# Schematic_Open-Book.net
KiCad netlist of a schematic drawn in EAGLE
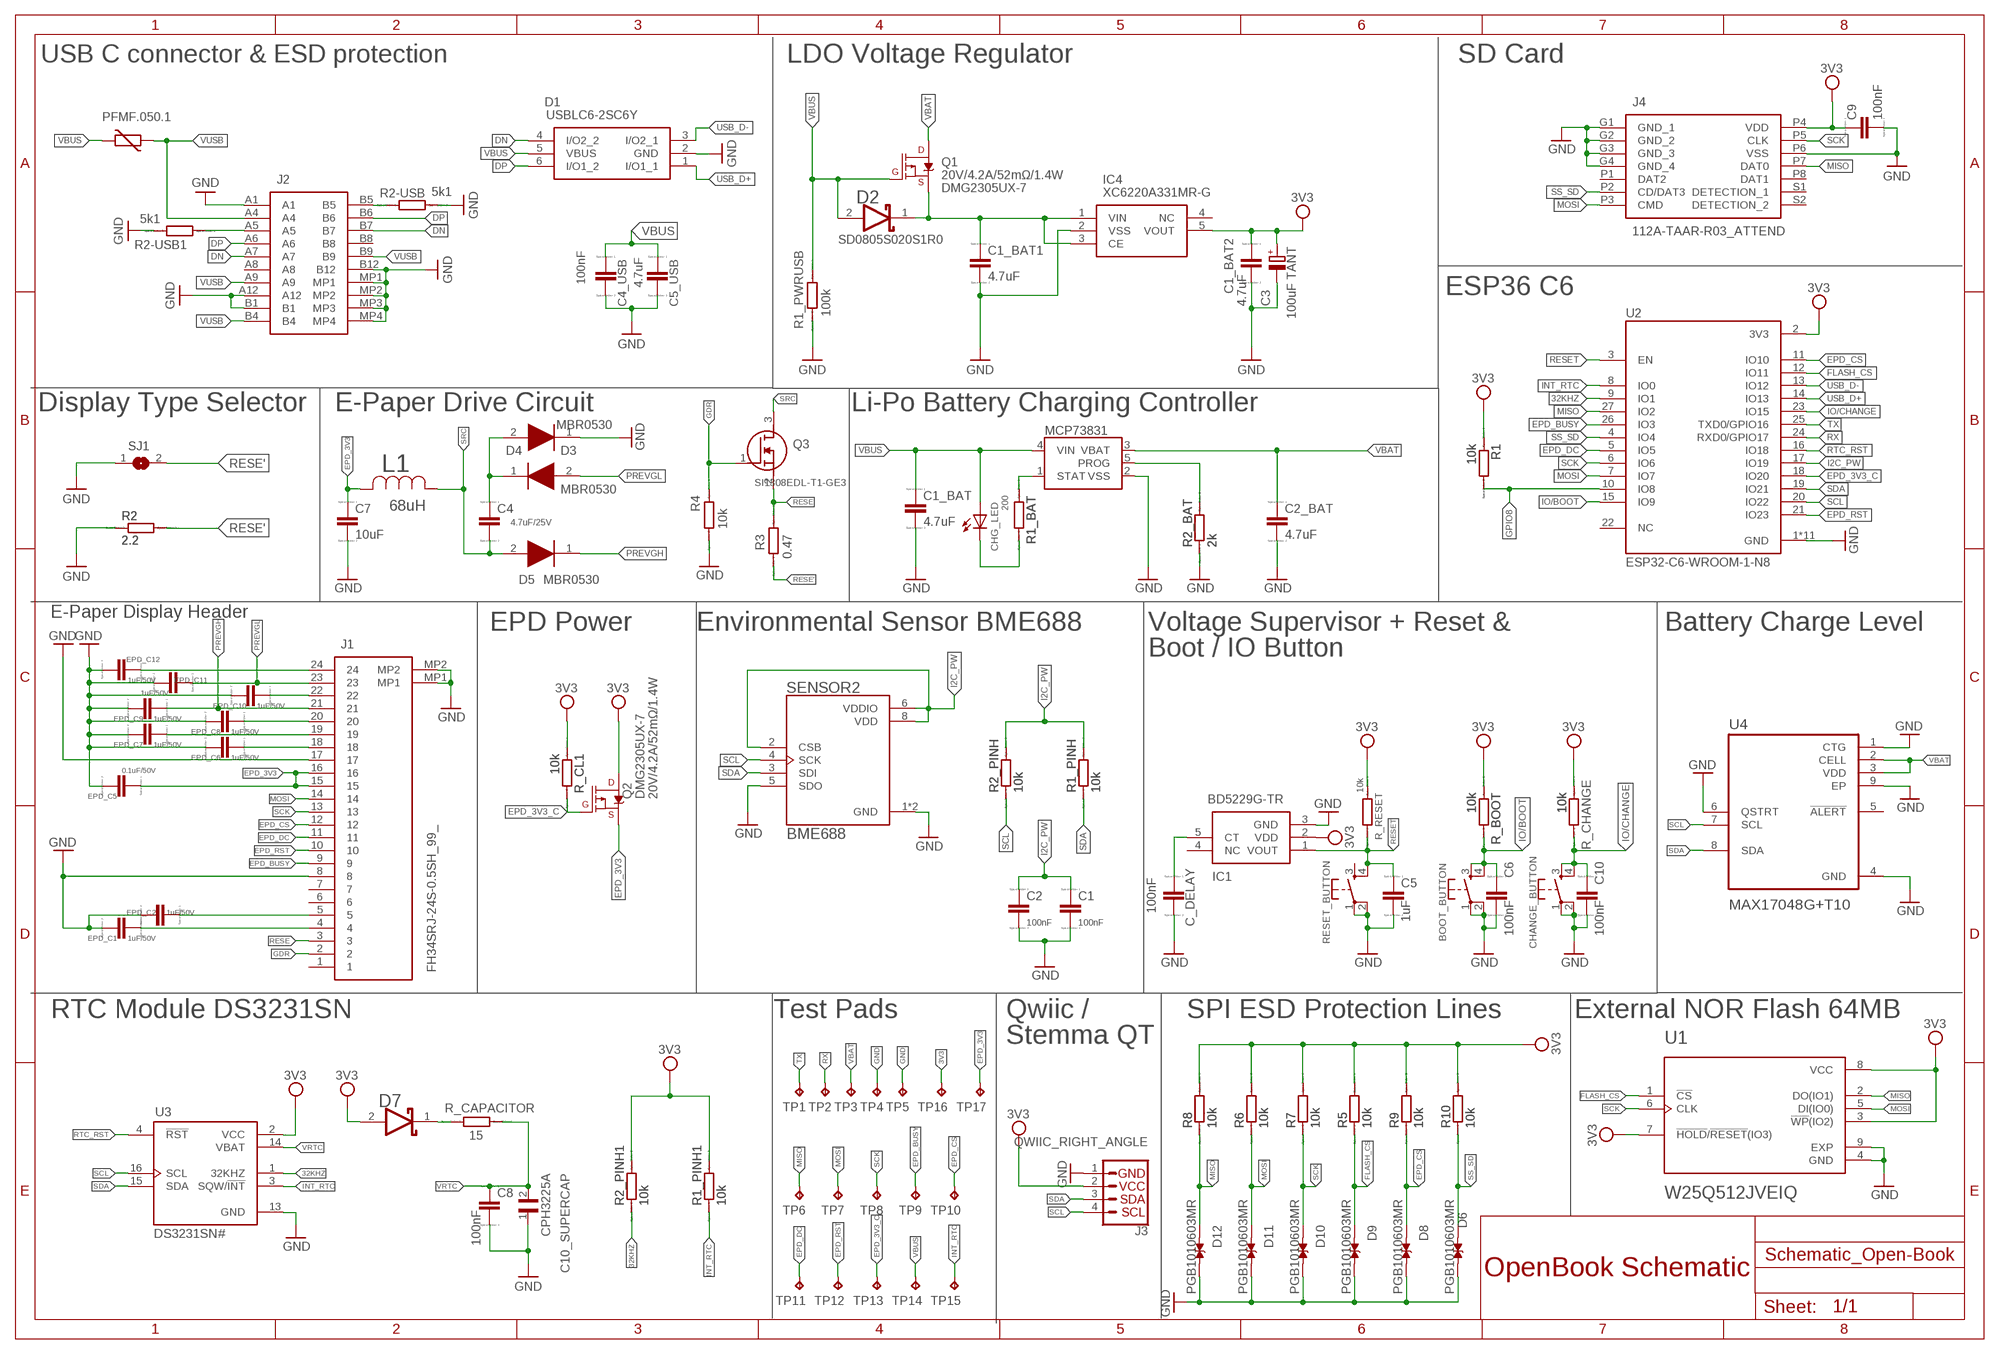
[diagram p0: schematic, sheet 1]

(export (version "E")
  (design (tool "Eeschema 10.0.6"))
  (components
    (comp (ref "BOOT_BUTTON")
      (value "BOOT_BUTTON")
      (footprint "eagle-import:MYBUTTON")
      (libsource (lib "eagle-import") (part "BUTTON_CUSYOMV1"))
    )
    (comp (ref "C1")
      (value "100nF")
      (footprint "eagle-import:ESP32_WROVER_EAGLE-LTSPICE_C0402")
      (libsource (lib "eagle-import") (part "ESP32_WROVER_EAGLE-LTSPICE_CC0402"))
    )
    (comp (ref "C1_BAT")
      (value "4.7uF")
      (footprint "eagle-import:ESP32_WROVER_EAGLE-LTSPICE_C0402")
      (libsource (lib "eagle-import") (part "ESP32_WROVER_EAGLE-LTSPICE_CC0402"))
    )
    (comp (ref "C1_BAT1")
      (value "4.7uF")
      (footprint "eagle-import:ESP32_WROVER_EAGLE-LTSPICE_C0402")
      (libsource (lib "eagle-import") (part "ESP32_WROVER_EAGLE-LTSPICE_CC0402"))
    )
    (comp (ref "C1_BAT2")
      (value "4.7uF")
      (footprint "eagle-import:ESP32_WROVER_EAGLE-LTSPICE_C0402")
      (libsource (lib "eagle-import") (part "ESP32_WROVER_EAGLE-LTSPICE_CC0402"))
    )
    (comp (ref "C2")
      (value "100nF")
      (footprint "eagle-import:ESP32_WROVER_EAGLE-LTSPICE_C0402")
      (libsource (lib "eagle-import") (part "ESP32_WROVER_EAGLE-LTSPICE_CC0402"))
    )
    (comp (ref "C2_BAT")
      (value "4.7uF")
      (footprint "eagle-import:ESP32_WROVER_EAGLE-LTSPICE_C0402")
      (libsource (lib "eagle-import") (part "ESP32_WROVER_EAGLE-LTSPICE_CC0402"))
    )
    (comp (ref "C3")
      (value "100uF TANT")
      (footprint "eagle-import:RCL_CT3528")
      (libsource (lib "eagle-import") (part "RCL_CPOL-EUCT3528"))
    )
    (comp (ref "C4")
      (value "4.7uF/25V")
      (footprint "eagle-import:ESP32_WROVER_EAGLE-LTSPICE_C0402")
      (libsource (lib "eagle-import") (part "ESP32_WROVER_EAGLE-LTSPICE_CC0402"))
    )
    (comp (ref "C4_USB")
      (value "100nF")
      (footprint "eagle-import:EAGLE-LTSPICE_C0402")
      (libsource (lib "eagle-import") (part "EAGLE-LTSPICE_CC0402"))
    )
    (comp (ref "C5")
      (value "1uF")
      (footprint "eagle-import:ESP32_WROVER_EAGLE-LTSPICE_C0402")
      (libsource (lib "eagle-import") (part "ESP32_WROVER_EAGLE-LTSPICE_CC0402"))
    )
    (comp (ref "C5_USB")
      (value "4.7uF")
      (footprint "eagle-import:EAGLE-LTSPICE_C0402")
      (libsource (lib "eagle-import") (part "EAGLE-LTSPICE_CC0402"))
    )
    (comp (ref "C6")
      (value "100nF")
      (footprint "eagle-import:ESP32_WROVER_EAGLE-LTSPICE_C0402")
      (libsource (lib "eagle-import") (part "ESP32_WROVER_EAGLE-LTSPICE_CC0402"))
    )
    (comp (ref "C7")
      (value "10uF")
      (footprint "eagle-import:ESP32_WROVER_EAGLE-LTSPICE_C0402")
      (libsource (lib "eagle-import") (part "ESP32_WROVER_EAGLE-LTSPICE_CC0402"))
    )
    (comp (ref "C8")
      (value "100nF")
      (footprint "eagle-import:ESP32_WROVER_EAGLE-LTSPICE_C0402")
      (libsource (lib "eagle-import") (part "ESP32_WROVER_EAGLE-LTSPICE_CC0402"))
    )
    (comp (ref "C9")
      (value "100nF")
      (footprint "eagle-import:ESP32_WROVER_EAGLE-LTSPICE_C0402")
      (libsource (lib "eagle-import") (part "ESP32_WROVER_EAGLE-LTSPICE_CC0402"))
    )
    (comp (ref "C10")
      (value "100nF")
      (footprint "eagle-import:ESP32_WROVER_EAGLE-LTSPICE_C0402")
      (libsource (lib "eagle-import") (part "ESP32_WROVER_EAGLE-LTSPICE_CC0402"))
    )
    (comp (ref "C10_SUPERCAP")
      (value "CPH3225A")
      (footprint "eagle-import:CAPCP3225X100N")
      (fields (field (name "MF") "Seiko Instruments"))
      (libsource (lib "eagle-import") (part "CPH3225A"))
    )
    (comp (ref "CHANGE_BUTTON")
      (value "CHANGE_BUTTON")
      (footprint "eagle-import:MYBUTTON")
      (libsource (lib "eagle-import") (part "BUTTON_CUSYOMV1"))
    )
    (comp (ref "CHG_LED")
      (value "ADAFRUIT_LEDCHIP-LED0603")
      (footprint "eagle-import:ADAFRUIT_CHIP-LED0603")
      (libsource (lib "eagle-import") (part "ADAFRUIT_LEDCHIP-LED0603"))
    )
    (comp (ref "C_DELAY")
      (value "100nF")
      (footprint "eagle-import:ESP32_WROVER_EAGLE-LTSPICE_C0402")
      (libsource (lib "eagle-import") (part "ESP32_WROVER_EAGLE-LTSPICE_CC0402"))
    )
    (comp (ref "D1")
      (value "USBLC6-2SC6Y")
      (footprint "eagle-import:SOT95P280X145-6N")
      (fields (field (name "MF") "STMicroelectronics"))
      (libsource (lib "eagle-import") (part "USBLC6-2SC6Y"))
    )
    (comp (ref "D2")
      (value "ESP32_WROVER_AVX---SD0805S020S1R0_AVX_SD0805S020S1R0_0_0AVX_SD0805S020S1R0_0_0")
      (footprint "eagle-import:ESP32_WROVER_AVX---SD0805S020S1R0_AVX_SD0805S020S1R0_0")
      (fields
        (field (name "DIGIKEY_PART_NUMBER") "478-7800-1-ND")
        (field (name "MF") "AVX")
        (field (name "MOUSER_PART_NUMBER") "581-SD0805S020S1R0")
      )
      (libsource (lib "eagle-import") (part "ESP32_WROVER_AVX---SD0805S020S1R0_AVX_SD0805S020S1R0_0_0AVX_SD0805S020S1R0_0_0"))
    )
    (comp (ref "D3")
      (value "MBR0530")
      (footprint "eagle-import:SOD3716X135N")
      (fields (field (name "MF") "ON Semiconductor"))
      (libsource (lib "eagle-import") (part "MBR0530"))
    )
    (comp (ref "D4")
      (value "MBR0530")
      (footprint "eagle-import:SOD3716X135N")
      (fields (field (name "MF") "ON Semiconductor"))
      (libsource (lib "eagle-import") (part "MBR0530"))
    )
    (comp (ref "D5")
      (value "MBR0530")
      (footprint "eagle-import:SOD3716X135N")
      (fields (field (name "MF") "ON Semiconductor"))
      (libsource (lib "eagle-import") (part "MBR0530"))
    )
    (comp (ref "D6")
      (value "PGB1010603MR")
      (footprint "eagle-import:DIOC1608X36N")
      (fields (field (name "MF") "Littelfuse Inc."))
      (libsource (lib "eagle-import") (part "PGB1010603MR"))
    )
    (comp (ref "D7")
      (value "ESP32_WROVER_AVX---SD0805S020S1R0_AVX_SD0805S020S1R0_0_0AVX_SD0805S020S1R0_0_0")
      (footprint "eagle-import:ESP32_WROVER_AVX---SD0805S020S1R0_AVX_SD0805S020S1R0_0")
      (fields
        (field (name "DIGIKEY_PART_NUMBER") "478-7800-1-ND")
        (field (name "MF") "AVX")
        (field (name "MOUSER_PART_NUMBER") "581-SD0805S020S1R0")
      )
      (libsource (lib "eagle-import") (part "ESP32_WROVER_AVX---SD0805S020S1R0_AVX_SD0805S020S1R0_0_0AVX_SD0805S020S1R0_0_0"))
    )
    (comp (ref "D8")
      (value "PGB1010603MR")
      (footprint "eagle-import:DIOC1608X36N")
      (fields (field (name "MF") "Littelfuse Inc."))
      (libsource (lib "eagle-import") (part "PGB1010603MR"))
    )
    (comp (ref "D9")
      (value "PGB1010603MR")
      (footprint "eagle-import:DIOC1608X36N")
      (fields (field (name "MF") "Littelfuse Inc."))
      (libsource (lib "eagle-import") (part "PGB1010603MR"))
    )
    (comp (ref "D10")
      (value "PGB1010603MR")
      (footprint "eagle-import:DIOC1608X36N")
      (fields (field (name "MF") "Littelfuse Inc."))
      (libsource (lib "eagle-import") (part "PGB1010603MR"))
    )
    (comp (ref "D11")
      (value "PGB1010603MR")
      (footprint "eagle-import:DIOC1608X36N")
      (fields (field (name "MF") "Littelfuse Inc."))
      (libsource (lib "eagle-import") (part "PGB1010603MR"))
    )
    (comp (ref "D12")
      (value "PGB1010603MR")
      (footprint "eagle-import:DIOC1608X36N")
      (fields (field (name "MF") "Littelfuse Inc."))
      (libsource (lib "eagle-import") (part "PGB1010603MR"))
    )
    (comp (ref "EPD_C1")
      (value "1uF/50V")
      (footprint "eagle-import:ESP32_WROVER_EAGLE-LTSPICE_C0402")
      (libsource (lib "eagle-import") (part "ESP32_WROVER_EAGLE-LTSPICE_CC0402"))
    )
    (comp (ref "EPD_C2")
      (value "1uF/50V")
      (footprint "eagle-import:ESP32_WROVER_EAGLE-LTSPICE_C0402")
      (libsource (lib "eagle-import") (part "ESP32_WROVER_EAGLE-LTSPICE_CC0402"))
    )
    (comp (ref "EPD_C5")
      (value "0.1uF/50V")
      (footprint "eagle-import:EAGLE-LTSPICE_C0402")
      (libsource (lib "eagle-import") (part "EAGLE-LTSPICE_CC0402"))
    )
    (comp (ref "EPD_C6")
      (value "1uF/50V")
      (footprint "eagle-import:EAGLE-LTSPICE_C0402")
      (libsource (lib "eagle-import") (part "EAGLE-LTSPICE_CC0402"))
    )
    (comp (ref "EPD_C7")
      (value "1uF/50V")
      (footprint "eagle-import:EAGLE-LTSPICE_C0402")
      (libsource (lib "eagle-import") (part "EAGLE-LTSPICE_CC0402"))
    )
    (comp (ref "EPD_C8")
      (value "1uF/50V")
      (footprint "eagle-import:EAGLE-LTSPICE_C0402")
      (libsource (lib "eagle-import") (part "EAGLE-LTSPICE_CC0402"))
    )
    (comp (ref "EPD_C9")
      (value "1uF/50V")
      (footprint "eagle-import:EAGLE-LTSPICE_C0402")
      (libsource (lib "eagle-import") (part "EAGLE-LTSPICE_CC0402"))
    )
    (comp (ref "EPD_C10")
      (value "1uF/50V")
      (footprint "eagle-import:EAGLE-LTSPICE_C0402")
      (libsource (lib "eagle-import") (part "EAGLE-LTSPICE_CC0402"))
    )
    (comp (ref "EPD_C11")
      (value "1uF/50V")
      (footprint "eagle-import:EAGLE-LTSPICE_C0402")
      (libsource (lib "eagle-import") (part "EAGLE-LTSPICE_CC0402"))
    )
    (comp (ref "EPD_C12")
      (value "1uF/50V")
      (footprint "eagle-import:EAGLE-LTSPICE_C0402")
      (libsource (lib "eagle-import") (part "EAGLE-LTSPICE_CC0402"))
    )
    (comp (ref "IC1")
      (value "BD5229G-TR")
      (footprint "eagle-import:SOT95P280X125-5N")
      (fields (field (name "MOUSER_PART_NUMBER") "755-BD5229G-TR"))
      (libsource (lib "eagle-import") (part "BD5229G-TR"))
    )
    (comp (ref "IC4")
      (value "XC6220A331MR-G")
      (footprint "eagle-import:SOT95P280X120-5N")
      (fields (field (name "MOUSER_PART_NUMBER") "865-XC6220A331MR-G"))
      (libsource (lib "eagle-import") (part "XC6220A331MR-G"))
    )
    (comp (ref "J1")
      (value "FH34SRJ-24S-0.5SH_99_")
      (footprint "eagle-import:FH34SRJ24S05SH99")
      (fields
        (field (name "MANUFACTURER_PART_NUMBER") "FH34SRJ-24S-0.5SH(99)")
        (field (name "MOUSER_PART_NUMBER") "798-FH34SRJ24S05SH99")
      )
      (libsource (lib "eagle-import") (part "FH34SRJ-24S-0.5SH_99_"))
    )
    (comp (ref "J2")
      (value "SAMACSYS_PARTS_USB4110-GF-A")
      (footprint "eagle-import:SAMACSYS_PARTS_USB4110GFA")
      (fields
        (field (name "MANUFACTURER_PART_NUMBER") "USB4110-GF-A")
        (field (name "MOUSER_PART_NUMBER") "640-USB4110-GF-A")
      )
      (libsource (lib "eagle-import") (part "SAMACSYS_PARTS_USB4110-GF-A"))
    )
    (comp (ref "J3")
      (value "QWIIC_RIGHT_ANGLE")
      (footprint "eagle-import:JST04_1MM_RA")
      (libsource (lib "eagle-import") (part "QWIIC_CONNECTORJS-1MM"))
    )
    (comp (ref "J4")
      (value "112A-TAAR-R03_ATTEND")
      (footprint "eagle-import:112ATAARR03ATTEND")
      (fields (field (name "MANUFACTURER_PART_NUMBER") "112A-TAAR-R03 ATTEND"))
      (libsource (lib "eagle-import") (part "112A-TAAR-R03_ATTEND"))
    )
    (comp (ref "L1")
      (value "68uH")
      (footprint "eagle-import:IND_4828-WE-TPC_WRE")
      (fields
        (field (name "MANUFACTURER_PART_NUMBER") "744043680")
        (field (name "COPYRIGHT") "Copyright (C) 2024 Ultra Librarian. All rights reserved.")
      )
      (libsource (lib "eagle-import") (part "744043680IND_4828-WE-TPC_WRE"))
    )
    (comp (ref "MCP73831")
      (value "ESP32_WROVER_SPARKFUN-IC-POWER_MCP73831")
      (footprint "eagle-import:ESP32_WROVER_SPARKFUN-IC-POWER_SOT23-5")
      (libsource (lib "eagle-import") (part "ESP32_WROVER_SPARKFUN-IC-POWER_MCP73831"))
    )
    (comp (ref "PFMF.050.1")
      (value "ESP32C6_VARISTORCN1812")
      (footprint "eagle-import:ESP32C6_VARISTOR_CT_CN1812")
      (libsource (lib "eagle-import") (part "ESP32C6_VARISTORCN1812"))
    )
    (comp (ref "Q1")
      (value "20V/4.2A/52mΩ/1.4W")
      (footprint "eagle-import:ESP32_WROVER_SPARKFUN-DISCRETESEMI_SOT23-3")
      (libsource (lib "eagle-import") (part "ESP32_WROVER_SPARKFUN-DISCRETESEMI_MOSFET_PCH-DMG2305UX-7"))
    )
    (comp (ref "Q2")
      (value "20V/4.2A/52mΩ/1.4W")
      (footprint "eagle-import:ESP32_WROVER_SPARKFUN-DISCRETESEMI_SOT23-3")
      (libsource (lib "eagle-import") (part "ESP32_WROVER_SPARKFUN-DISCRETESEMI_MOSFET_PCH-DMG2305UX-7"))
    )
    (comp (ref "Q3")
      (value "SI1308EDL-T1-GE3")
      (footprint "eagle-import:SOT65P210X110-3N")
      (fields (field (name "MF") "Vishay Siliconix"))
      (libsource (lib "eagle-import") (part "SI1308EDL-T1-GE3"))
    )
    (comp (ref "R1")
      (value "10k")
      (footprint "eagle-import:ESP32_WROVER_EAGLE-LTSPICE_R0402")
      (libsource (lib "eagle-import") (part "ESP32_WROVER_EAGLE-LTSPICE_RR0402"))
    )
    (comp (ref "R1_BAT")
      (value "200")
      (footprint "eagle-import:ESP32_WROVER_EAGLE-LTSPICE_R0402")
      (libsource (lib "eagle-import") (part "ESP32_WROVER_EAGLE-LTSPICE_RR0402"))
    )
    (comp (ref "R1_PINH")
      (value "10k")
      (footprint "eagle-import:ESP32_WROVER_EAGLE-LTSPICE_R0402")
      (libsource (lib "eagle-import") (part "ESP32_WROVER_EAGLE-LTSPICE_RR0402"))
    )
    (comp (ref "R1_PINH1")
      (value "10k")
      (footprint "eagle-import:ESP32_WROVER_EAGLE-LTSPICE_R0402")
      (libsource (lib "eagle-import") (part "ESP32_WROVER_EAGLE-LTSPICE_RR0402"))
    )
    (comp (ref "R1_PWRUSB")
      (value "100k")
      (footprint "eagle-import:ESP32_WROVER_EAGLE-LTSPICE_R0402")
      (libsource (lib "eagle-import") (part "ESP32_WROVER_EAGLE-LTSPICE_RR0402"))
    )
    (comp (ref "R2")
      (value "2.2")
      (footprint "eagle-import:ESP32_WROVER_EAGLE-LTSPICE_R0402")
      (libsource (lib "eagle-import") (part "ESP32_WROVER_EAGLE-LTSPICE_RR0402"))
    )
    (comp (ref "R2-USB")
      (value "5k1")
      (footprint "eagle-import:ESP32_WROVER_EAGLE-LTSPICE_R0402")
      (libsource (lib "eagle-import") (part "ESP32_WROVER_EAGLE-LTSPICE_RR0402"))
    )
    (comp (ref "R2-USB1")
      (value "5k1")
      (footprint "eagle-import:ESP32_WROVER_EAGLE-LTSPICE_R0402")
      (libsource (lib "eagle-import") (part "ESP32_WROVER_EAGLE-LTSPICE_RR0402"))
    )
    (comp (ref "R2_BAT")
      (value "2k")
      (footprint "eagle-import:ESP32_WROVER_EAGLE-LTSPICE_R0402")
      (libsource (lib "eagle-import") (part "ESP32_WROVER_EAGLE-LTSPICE_RR0402"))
    )
    (comp (ref "R2_PINH")
      (value "10k")
      (footprint "eagle-import:ESP32_WROVER_EAGLE-LTSPICE_R0402")
      (libsource (lib "eagle-import") (part "ESP32_WROVER_EAGLE-LTSPICE_RR0402"))
    )
    (comp (ref "R2_PINH1")
      (value "10k")
      (footprint "eagle-import:ESP32_WROVER_EAGLE-LTSPICE_R0402")
      (libsource (lib "eagle-import") (part "ESP32_WROVER_EAGLE-LTSPICE_RR0402"))
    )
    (comp (ref "R3")
      (value "0.47")
      (footprint "eagle-import:ESP32_WROVER_EAGLE-LTSPICE_R0402")
      (libsource (lib "eagle-import") (part "ESP32_WROVER_EAGLE-LTSPICE_RR0402"))
    )
    (comp (ref "R4")
      (value "10k")
      (footprint "eagle-import:ESP32_WROVER_EAGLE-LTSPICE_R0402")
      (libsource (lib "eagle-import") (part "ESP32_WROVER_EAGLE-LTSPICE_RR0402"))
    )
    (comp (ref "R5")
      (value "10k")
      (footprint "eagle-import:ESP32_WROVER_EAGLE-LTSPICE_R0402")
      (libsource (lib "eagle-import") (part "ESP32_WROVER_EAGLE-LTSPICE_RR0402"))
    )
    (comp (ref "R6")
      (value "10k")
      (footprint "eagle-import:ESP32_WROVER_EAGLE-LTSPICE_R0402")
      (libsource (lib "eagle-import") (part "ESP32_WROVER_EAGLE-LTSPICE_RR0402"))
    )
    (comp (ref "R7")
      (value "10k")
      (footprint "eagle-import:ESP32_WROVER_EAGLE-LTSPICE_R0402")
      (libsource (lib "eagle-import") (part "ESP32_WROVER_EAGLE-LTSPICE_RR0402"))
    )
    (comp (ref "R8")
      (value "10k")
      (footprint "eagle-import:ESP32_WROVER_EAGLE-LTSPICE_R0402")
      (libsource (lib "eagle-import") (part "ESP32_WROVER_EAGLE-LTSPICE_RR0402"))
    )
    (comp (ref "R9")
      (value "10k")
      (footprint "eagle-import:ESP32_WROVER_EAGLE-LTSPICE_R0402")
      (libsource (lib "eagle-import") (part "ESP32_WROVER_EAGLE-LTSPICE_RR0402"))
    )
    (comp (ref "R10")
      (value "10k")
      (footprint "eagle-import:ESP32_WROVER_EAGLE-LTSPICE_R0402")
      (libsource (lib "eagle-import") (part "ESP32_WROVER_EAGLE-LTSPICE_RR0402"))
    )
    (comp (ref "RESET_BUTTON")
      (value "RESET_BUTTON")
      (footprint "eagle-import:MYBUTTON")
      (libsource (lib "eagle-import") (part "BUTTON_CUSYOMV1"))
    )
    (comp (ref "R_BOOT")
      (value "10k")
      (footprint "eagle-import:ESP32_WROVER_EAGLE-LTSPICE_R0402")
      (libsource (lib "eagle-import") (part "ESP32_WROVER_EAGLE-LTSPICE_RR0402"))
    )
    (comp (ref "R_CAPACITOR")
      (value "15")
      (footprint "eagle-import:ESP32_WROVER_EAGLE-LTSPICE_R0402")
      (libsource (lib "eagle-import") (part "ESP32_WROVER_EAGLE-LTSPICE_RR0402"))
    )
    (comp (ref "R_CHANGE")
      (value "10k")
      (footprint "eagle-import:ESP32_WROVER_EAGLE-LTSPICE_R0402")
      (libsource (lib "eagle-import") (part "ESP32_WROVER_EAGLE-LTSPICE_RR0402"))
    )
    (comp (ref "R_CL1")
      (value "10k")
      (footprint "eagle-import:ESP32_WROVER_EAGLE-LTSPICE_R0402")
      (libsource (lib "eagle-import") (part "ESP32_WROVER_EAGLE-LTSPICE_RR0402"))
    )
    (comp (ref "R_RESET")
      (value "10k")
      (footprint "eagle-import:ESP32_WROVER_EAGLE-LTSPICE_R0402")
      (libsource (lib "eagle-import") (part "ESP32_WROVER_EAGLE-LTSPICE_RR0402"))
    )
    (comp (ref "SENSOR2")
      (value "BME688")
      (footprint "eagle-import:ESP32_WROVER_BME680_PSON80P300X300X100-8N")
      (fields (field (name "MF") "Bosch Sensortec") (field (name "MP") "BME680"))
      (libsource (lib "eagle-import") (part "ESP32_WROVER_BME680_BME680"))
    )
    (comp (ref "SJ1") (value "SJ") (footprint "eagle-import:SJ") (libsource (lib "eagle-import") (part "SJ")))
    (comp (ref "TP1")
      (value "TPTP20R")
      (footprint "eagle-import:TP20R")
      (libsource (lib "eagle-import") (part "TPTP20R"))
    )
    (comp (ref "TP2")
      (value "TPTP20R")
      (footprint "eagle-import:TP20R")
      (libsource (lib "eagle-import") (part "TPTP20R"))
    )
    (comp (ref "TP3")
      (value "TPTP20R")
      (footprint "eagle-import:TP20R")
      (libsource (lib "eagle-import") (part "TPTP20R"))
    )
    (comp (ref "TP4")
      (value "TPTP20R")
      (footprint "eagle-import:TP20R")
      (libsource (lib "eagle-import") (part "TPTP20R"))
    )
    (comp (ref "TP5")
      (value "TPTP20R")
      (footprint "eagle-import:TP20R")
      (libsource (lib "eagle-import") (part "TPTP20R"))
    )
    (comp (ref "TP6")
      (value "TPTP20R")
      (footprint "eagle-import:TP20R")
      (libsource (lib "eagle-import") (part "TPTP20R"))
    )
    (comp (ref "TP7")
      (value "TPTP20R")
      (footprint "eagle-import:TP20R")
      (libsource (lib "eagle-import") (part "TPTP20R"))
    )
    (comp (ref "TP8")
      (value "TPTP20R")
      (footprint "eagle-import:TP20R")
      (libsource (lib "eagle-import") (part "TPTP20R"))
    )
    (comp (ref "TP9")
      (value "TPTP20R")
      (footprint "eagle-import:TP20R")
      (libsource (lib "eagle-import") (part "TPTP20R"))
    )
    (comp (ref "TP10")
      (value "TPTP20R")
      (footprint "eagle-import:TP20R")
      (libsource (lib "eagle-import") (part "TPTP20R"))
    )
    (comp (ref "TP11")
      (value "TPTP20R")
      (footprint "eagle-import:TP20R")
      (libsource (lib "eagle-import") (part "TPTP20R"))
    )
    (comp (ref "TP12")
      (value "TPTP20R")
      (footprint "eagle-import:TP20R")
      (libsource (lib "eagle-import") (part "TPTP20R"))
    )
    (comp (ref "TP13")
      (value "TPTP20R")
      (footprint "eagle-import:TP20R")
      (libsource (lib "eagle-import") (part "TPTP20R"))
    )
    (comp (ref "TP14")
      (value "TPTP20R")
      (footprint "eagle-import:TP20R")
      (libsource (lib "eagle-import") (part "TPTP20R"))
    )
    (comp (ref "TP15")
      (value "TPTP20R")
      (footprint "eagle-import:TP20R")
      (libsource (lib "eagle-import") (part "TPTP20R"))
    )
    (comp (ref "TP16")
      (value "TPTP20R")
      (footprint "eagle-import:TP20R")
      (libsource (lib "eagle-import") (part "TPTP20R"))
    )
    (comp (ref "TP17")
      (value "TPTP20R")
      (footprint "eagle-import:TP20R")
      (libsource (lib "eagle-import") (part "TPTP20R"))
    )
    (comp (ref "U1")
      (value "W25Q512JVEIQ")
      (footprint "eagle-import:SON127P600X800X80-9N")
      (fields (field (name "MF") "Winbond Electronics"))
      (libsource (lib "eagle-import") (part "W25Q512JVEIQ"))
    )
    (comp (ref "U2")
      (value "ESP32-C6-WROOM-1-N8")
      (footprint "eagle-import:XCVR_ESP32-C6-WROOM-1-N8")
      (fields (field (name "MF") "Espressif Systems"))
      (libsource (lib "eagle-import") (part "ESP32-C6-WROOM-1-N8"))
    )
    (comp (ref "U3")
      (value "DS3231SN#")
      (footprint "eagle-import:SOIC127P1032X265-16N")
      (fields (field (name "MF") "Analog Devices"))
      (libsource (lib "eagle-import") (part "DS3231SN#"))
    )
    (comp (ref "U4")
      (value "MAX17048G+T10")
      (footprint "eagle-import:SON50P200X200X80-9N")
      (fields (field (name "MF") "Analog Devices"))
      (libsource (lib "eagle-import") (part "MAX17048G+T10"))
    )
  )
  (nets
    (net (code "1") (name "3V3") (class "Default")
      (node (ref "C1_BAT2") (pin "1") (pinfunction "1_1") (pintype "passive"))
      (node (ref "C3") (pin "+") (pinfunction "+_+") (pintype "passive"))
      (node (ref "C9") (pin "1") (pinfunction "1_1") (pintype "passive"))
      (node (ref "D7") (pin "2") (pinfunction "ANODE_2") (pintype "bidirectional"))
      (node (ref "IC1") (pin "2") (pinfunction "VDD_2") (pintype "bidirectional"))
      (node (ref "IC4") (pin "5") (pinfunction "VOUT_5") (pintype "bidirectional"))
      (node (ref "J3") (pin "2") (pinfunction "2_2") (pintype "power_in"))
      (node (ref "J4") (pin "P4") (pinfunction "VDD_P4") (pintype "bidirectional"))
      (node (ref "Q2") (pin "3") (pinfunction "D_3") (pintype "bidirectional"))
      (node (ref "R1") (pin "1") (pinfunction "1_1") (pintype "passive"))
      (node (ref "R10") (pin "2") (pinfunction "2_2") (pintype "passive"))
      (node (ref "R1_PINH1") (pin "2") (pinfunction "2_2") (pintype "passive"))
      (node (ref "R2_PINH1") (pin "2") (pinfunction "2_2") (pintype "passive"))
      (node (ref "R5") (pin "2") (pinfunction "2_2") (pintype "passive"))
      (node (ref "R6") (pin "2") (pinfunction "2_2") (pintype "passive"))
      (node (ref "R7") (pin "2") (pinfunction "2_2") (pintype "passive"))
      (node (ref "R8") (pin "2") (pinfunction "2_2") (pintype "passive"))
      (node (ref "R9") (pin "2") (pinfunction "2_2") (pintype "passive"))
      (node (ref "R_BOOT") (pin "1") (pinfunction "1_1") (pintype "passive"))
      (node (ref "R_CHANGE") (pin "1") (pinfunction "1_1") (pintype "passive"))
      (node (ref "R_CL1") (pin "1") (pinfunction "1_1") (pintype "passive"))
      (node (ref "R_RESET") (pin "1") (pinfunction "1_1") (pintype "passive"))
      (node (ref "TP16") (pin "TP") (pinfunction "TP_TP") (pintype "input"))
      (node (ref "U1") (pin "3") (pinfunction "~{WP}(IO2)_3") (pintype "bidirectional"))
      (node (ref "U1") (pin "7") (pinfunction "~{HOLD}/~{RESET}(IO3)_7") (pintype "bidirectional"))
      (node (ref "U1") (pin "8") (pinfunction "VCC_8") (pintype "power_in"))
      (node (ref "U2") (pin "2") (pinfunction "3V3_2") (pintype "power_in"))
      (node (ref "U3") (pin "2") (pinfunction "VCC_2") (pintype "power_in"))
    )
    (net (code "2") (name "32KHZ") (class "Default")
      (node (ref "R2_PINH1") (pin "1") (pinfunction "1_1") (pintype "passive"))
      (node (ref "U2") (pin "9") (pinfunction "IO1_9") (pintype "bidirectional"))
      (node (ref "U3") (pin "1") (pinfunction "32KHZ_1") (pintype "output"))
    )
    (net (code "3") (name "DN") (class "Default")
      (node (ref "D1") (pin "4") (pinfunction "I/O2_2_4") (pintype "bidirectional"))
      (node (ref "J2") (pin "A7") (pinfunction "A7_A7") (pintype "bidirectional"))
      (node (ref "J2") (pin "B7") (pinfunction "B7_B7") (pintype "bidirectional"))
    )
    (net (code "4") (name "DP") (class "Default")
      (node (ref "D1") (pin "6") (pinfunction "I/O1_2_6") (pintype "bidirectional"))
      (node (ref "J2") (pin "A6") (pinfunction "A6_A6") (pintype "bidirectional"))
      (node (ref "J2") (pin "B6") (pinfunction "B6_B6") (pintype "bidirectional"))
    )
    (net (code "5") (name "EPD_3V3") (class "Default")
      (node (ref "C7") (pin "1") (pinfunction "1_1") (pintype "passive"))
      (node (ref "EPD_C5") (pin "1") (pinfunction "1_1") (pintype "passive"))
      (node (ref "J1") (pin "15") (pinfunction "15_15") (pintype "bidirectional"))
      (node (ref "J1") (pin "16") (pinfunction "16_16") (pintype "bidirectional"))
      (node (ref "L1") (pin "2") (pinfunction "2_2") (pintype "passive"))
      (node (ref "Q2") (pin "2") (pinfunction "S_2") (pintype "bidirectional"))
      (node (ref "TP17") (pin "TP") (pinfunction "TP_TP") (pintype "input"))
    )
    (net (code "6") (name "EPD_3V3_C") (class "Default")
      (node (ref "Q2") (pin "1") (pinfunction "G_1") (pintype "bidirectional"))
      (node (ref "R_CL1") (pin "2") (pinfunction "2_2") (pintype "passive"))
      (node (ref "TP13") (pin "TP") (pinfunction "TP_TP") (pintype "input"))
      (node (ref "U2") (pin "18") (pinfunction "IO20_18") (pintype "bidirectional"))
    )
    (net (code "7") (name "EPD_BUSY") (class "Default")
      (node (ref "J1") (pin "9") (pinfunction "9_9") (pintype "bidirectional"))
      (node (ref "TP9") (pin "TP") (pinfunction "TP_TP") (pintype "input"))
      (node (ref "U2") (pin "26") (pinfunction "IO3_26") (pintype "bidirectional"))
    )
    (net (code "8") (name "EPD_CS") (class "Default")
      (node (ref "D8") (pin "1") (pinfunction "1_1") (pintype "passive"))
      (node (ref "J1") (pin "12") (pinfunction "12_12") (pintype "bidirectional"))
      (node (ref "R9") (pin "1") (pinfunction "1_1") (pintype "passive"))
      (node (ref "TP10") (pin "TP") (pinfunction "TP_TP") (pintype "input"))
      (node (ref "U2") (pin "11") (pinfunction "IO10_11") (pintype "bidirectional"))
    )
    (net (code "9") (name "EPD_DC") (class "Default")
      (node (ref "J1") (pin "11") (pinfunction "11_11") (pintype "bidirectional"))
      (node (ref "TP11") (pin "TP") (pinfunction "TP_TP") (pintype "input"))
      (node (ref "U2") (pin "5") (pinfunction "IO5_5") (pintype "bidirectional"))
    )
    (net (code "10") (name "EPD_RST") (class "Default")
      (node (ref "J1") (pin "10") (pinfunction "10_10") (pintype "bidirectional"))
      (node (ref "TP12") (pin "TP") (pinfunction "TP_TP") (pintype "input"))
      (node (ref "U2") (pin "21") (pinfunction "IO23_21") (pintype "bidirectional"))
    )
    (net (code "11") (name "FLASH_CS") (class "Default")
      (node (ref "D9") (pin "1") (pinfunction "1_1") (pintype "passive"))
      (node (ref "R5") (pin "1") (pinfunction "1_1") (pintype "passive"))
      (node (ref "U1") (pin "1") (pinfunction "~{CS}_1") (pintype "input"))
      (node (ref "U2") (pin "12") (pinfunction "IO11_12") (pintype "bidirectional"))
    )
    (net (code "12") (name "GDR") (class "Default")
      (node (ref "J1") (pin "2") (pinfunction "2_2") (pintype "bidirectional"))
      (node (ref "Q3") (pin "1") (pinfunction "G_1") (pintype "bidirectional"))
      (node (ref "R4") (pin "1") (pinfunction "1_1") (pintype "passive"))
    )
    (net (code "13") (name "GND") (class "Default")
      (node (ref "BOOT_BUTTON") (pin "1") (pinfunction "1_1") (pintype "passive"))
      (node (ref "BOOT_BUTTON") (pin "2") (pinfunction "2_2") (pintype "passive"))
      (node (ref "C1") (pin "2") (pinfunction "2_2") (pintype "passive"))
      (node (ref "C10") (pin "2") (pinfunction "2_2") (pintype "passive"))
      (node (ref "C10_SUPERCAP") (pin "1") (pinfunction "1_1") (pintype "passive"))
      (node (ref "C1_BAT") (pin "2") (pinfunction "2_2") (pintype "passive"))
      (node (ref "C1_BAT1") (pin "2") (pinfunction "2_2") (pintype "passive"))
      (node (ref "C1_BAT2") (pin "2") (pinfunction "2_2") (pintype "passive"))
      (node (ref "C2") (pin "2") (pinfunction "2_2") (pintype "passive"))
      (node (ref "C2_BAT") (pin "2") (pinfunction "2_2") (pintype "passive"))
      (node (ref "C3") (pin "-") (pinfunction "-_-") (pintype "passive"))
      (node (ref "C4_USB") (pin "2") (pinfunction "2_2") (pintype "passive"))
      (node (ref "C5") (pin "2") (pinfunction "2_2") (pintype "passive"))
      (node (ref "C5_USB") (pin "2") (pinfunction "2_2") (pintype "passive"))
      (node (ref "C6") (pin "2") (pinfunction "2_2") (pintype "passive"))
      (node (ref "C7") (pin "2") (pinfunction "2_2") (pintype "passive"))
      (node (ref "C8") (pin "2") (pinfunction "2_2") (pintype "passive"))
      (node (ref "C9") (pin "2") (pinfunction "2_2") (pintype "passive"))
      (node (ref "CHANGE_BUTTON") (pin "1") (pinfunction "1_1") (pintype "passive"))
      (node (ref "CHANGE_BUTTON") (pin "2") (pinfunction "2_2") (pintype "passive"))
      (node (ref "C_DELAY") (pin "2") (pinfunction "2_2") (pintype "passive"))
      (node (ref "D1") (pin "2") (pinfunction "GND_2") (pintype "bidirectional"))
      (node (ref "D10") (pin "2") (pinfunction "2_2") (pintype "passive"))
      (node (ref "D11") (pin "2") (pinfunction "2_2") (pintype "passive"))
      (node (ref "D12") (pin "2") (pinfunction "2_2") (pintype "passive"))
      (node (ref "D4") (pin "1") (pinfunction "K_1") (pintype "bidirectional"))
      (node (ref "D6") (pin "2") (pinfunction "2_2") (pintype "passive"))
      (node (ref "D8") (pin "2") (pinfunction "2_2") (pintype "passive"))
      (node (ref "D9") (pin "2") (pinfunction "2_2") (pintype "passive"))
      (node (ref "EPD_C1") (pin "2") (pinfunction "2_2") (pintype "passive"))
      (node (ref "EPD_C10") (pin "2") (pinfunction "2_2") (pintype "passive"))
      (node (ref "EPD_C11") (pin "2") (pinfunction "2_2") (pintype "passive"))
      (node (ref "EPD_C12") (pin "2") (pinfunction "2_2") (pintype "passive"))
      (node (ref "EPD_C2") (pin "2") (pinfunction "2_2") (pintype "passive"))
      (node (ref "EPD_C5") (pin "2") (pinfunction "2_2") (pintype "passive"))
      (node (ref "EPD_C6") (pin "2") (pinfunction "2_2") (pintype "passive"))
      (node (ref "EPD_C7") (pin "2") (pinfunction "2_2") (pintype "passive"))
      (node (ref "EPD_C8") (pin "2") (pinfunction "2_2") (pintype "passive"))
      (node (ref "EPD_C9") (pin "2") (pinfunction "2_2") (pintype "passive"))
      (node (ref "IC1") (pin "3") (pinfunction "GND_3") (pintype "bidirectional"))
      (node (ref "IC4") (pin "2") (pinfunction "VSS_2") (pintype "bidirectional"))
      (node (ref "J1") (pin "17") (pinfunction "17_17") (pintype "bidirectional"))
      (node (ref "J1") (pin "8") (pinfunction "8_8") (pintype "bidirectional"))
      (node (ref "J1") (pin "MP1") (pinfunction "MP1_MP1") (pintype "bidirectional"))
      (node (ref "J1") (pin "MP2") (pinfunction "MP2_MP2") (pintype "bidirectional"))
      (node (ref "J2") (pin "A1") (pinfunction "A1_A1") (pintype "bidirectional"))
      (node (ref "J2") (pin "A12") (pinfunction "A12_A12") (pintype "bidirectional"))
      (node (ref "J2") (pin "B1") (pinfunction "B1_B1") (pintype "bidirectional"))
      (node (ref "J2") (pin "B12") (pinfunction "B12_B12") (pintype "bidirectional"))
      (node (ref "J2") (pin "MP1") (pinfunction "MP1_MP1") (pintype "bidirectional"))
      (node (ref "J2") (pin "MP2") (pinfunction "MP2_MP2") (pintype "bidirectional"))
      (node (ref "J2") (pin "MP3") (pinfunction "MP3_MP3") (pintype "bidirectional"))
      (node (ref "J2") (pin "MP4") (pinfunction "MP4_MP4") (pintype "bidirectional"))
      (node (ref "J3") (pin "1") (pinfunction "1_1") (pintype "power_in"))
      (node (ref "J4") (pin "G1") (pinfunction "GND_1_G1") (pintype "bidirectional"))
      (node (ref "J4") (pin "G2") (pinfunction "GND_2_G2") (pintype "bidirectional"))
      (node (ref "J4") (pin "G3") (pinfunction "GND_3_G3") (pintype "bidirectional"))
      (node (ref "J4") (pin "G4") (pinfunction "GND_4_G4") (pintype "bidirectional"))
      (node (ref "J4") (pin "P6") (pinfunction "VSS_P6") (pintype "bidirectional"))
      (node (ref "MCP73831") (pin "2") (pinfunction "VSS_2") (pintype "power_in"))
      (node (ref "R1_PWRUSB") (pin "2") (pinfunction "2_2") (pintype "passive"))
      (node (ref "R2") (pin "1") (pinfunction "1_1") (pintype "passive"))
      (node (ref "R2-USB") (pin "2") (pinfunction "2_2") (pintype "passive"))
      (node (ref "R2-USB1") (pin "1") (pinfunction "1_1") (pintype "passive"))
      (node (ref "R2_BAT") (pin "1") (pinfunction "1_1") (pintype "passive"))
      (node (ref "R4") (pin "2") (pinfunction "2_2") (pintype "passive"))
      (node (ref "RESET_BUTTON") (pin "1") (pinfunction "1_1") (pintype "passive"))
      (node (ref "RESET_BUTTON") (pin "2") (pinfunction "2_2") (pintype "passive"))
      (node (ref "SENSOR2") (pin "1") (pinfunction "GND_1") (pintype "power_in"))
      (node (ref "SENSOR2") (pin "5") (pinfunction "SDO_5") (pintype "bidirectional"))
      (node (ref "SENSOR2") (pin "7") (pinfunction "GND_7") (pintype "power_in"))
      (node (ref "SJ1") (pin "1") (pinfunction "1_1") (pintype "passive"))
      (node (ref "TP4") (pin "TP") (pinfunction "TP_TP") (pintype "input"))
      (node (ref "TP5") (pin "TP") (pinfunction "TP_TP") (pintype "input"))
      (node (ref "U1") (pin "4") (pinfunction "GND_4") (pintype "power_in"))
      (node (ref "U1") (pin "9") (pinfunction "EXP_9") (pintype "passive"))
      (node (ref "U2") (pin "1") (pinfunction "GND_1") (pintype "power_in"))
      (node (ref "U2") (pin "28") (pinfunction "GND_28") (pintype "power_in"))
      (node (ref "U2") (pin "29_1") (pinfunction "GND_29_1") (pintype "power_in"))
      (node (ref "U2") (pin "29_2") (pinfunction "GND_29_2") (pintype "power_in"))
      (node (ref "U2") (pin "29_3") (pinfunction "GND_29_3") (pintype "power_in"))
      (node (ref "U2") (pin "29_4") (pinfunction "GND_29_4") (pintype "power_in"))
      (node (ref "U2") (pin "29_5") (pinfunction "GND_29_5") (pintype "power_in"))
      (node (ref "U2") (pin "29_6") (pinfunction "GND_29_6") (pintype "power_in"))
      (node (ref "U2") (pin "29_7") (pinfunction "GND_29_7") (pintype "power_in"))
      (node (ref "U2") (pin "29_8") (pinfunction "GND_29_8") (pintype "power_in"))
      (node (ref "U2") (pin "29_9") (pinfunction "GND_29_9") (pintype "power_in"))
      (node (ref "U3") (pin "13") (pinfunction "GND_13") (pintype "power_in"))
      (node (ref "U4") (pin "1") (pinfunction "CTG_1") (pintype "power_in"))
      (node (ref "U4") (pin "4") (pinfunction "GND_4") (pintype "power_in"))
      (node (ref "U4") (pin "6") (pinfunction "QSTRT_6") (pintype "input"))
      (node (ref "U4") (pin "9") (pinfunction "EP_9") (pintype "power_in"))
    )
    (net (code "14") (name "GPIO8") (class "Default")
      (node (ref "R1") (pin "2") (pinfunction "2_2") (pintype "passive"))
      (node (ref "U2") (pin "10") (pinfunction "IO8_10") (pintype "bidirectional"))
    )
    (net (code "15") (name "I2C_PW") (class "Default")
      (node (ref "C1") (pin "1") (pinfunction "1_1") (pintype "passive"))
      (node (ref "C2") (pin "1") (pinfunction "1_1") (pintype "passive"))
      (node (ref "R1_PINH") (pin "2") (pinfunction "2_2") (pintype "passive"))
      (node (ref "R2_PINH") (pin "2") (pinfunction "2_2") (pintype "passive"))
      (node (ref "SENSOR2") (pin "2") (pinfunction "CSB_2") (pintype "input"))
      (node (ref "SENSOR2") (pin "6") (pinfunction "VDDIO_6") (pintype "power_in"))
      (node (ref "SENSOR2") (pin "8") (pinfunction "VDD_8") (pintype "power_in"))
      (node (ref "U2") (pin "17") (pinfunction "IO19_17") (pintype "bidirectional"))
    )
    (net (code "16") (name "INT_RTC") (class "Default")
      (node (ref "R1_PINH1") (pin "1") (pinfunction "1_1") (pintype "passive"))
      (node (ref "TP15") (pin "TP") (pinfunction "TP_TP") (pintype "input"))
      (node (ref "U2") (pin "8") (pinfunction "IO0_8") (pintype "bidirectional"))
      (node (ref "U3") (pin "3") (pinfunction "SQW/~{INT}_3") (pintype "output"))
    )
    (net (code "17") (name "IO{slash}BOOT") (class "Default")
      (node (ref "BOOT_BUTTON") (pin "3") (pinfunction "3_3") (pintype "passive"))
      (node (ref "BOOT_BUTTON") (pin "4") (pinfunction "4_4") (pintype "passive"))
      (node (ref "C6") (pin "1") (pinfunction "1_1") (pintype "passive"))
      (node (ref "R_BOOT") (pin "2") (pinfunction "2_2") (pintype "passive"))
      (node (ref "U2") (pin "15") (pinfunction "IO9_15") (pintype "bidirectional"))
    )
    (net (code "18") (name "IO{slash}CHANGE") (class "Default")
      (node (ref "C10") (pin "1") (pinfunction "1_1") (pintype "passive"))
      (node (ref "CHANGE_BUTTON") (pin "3") (pinfunction "3_3") (pintype "passive"))
      (node (ref "CHANGE_BUTTON") (pin "4") (pinfunction "4_4") (pintype "passive"))
      (node (ref "R_CHANGE") (pin "2") (pinfunction "2_2") (pintype "passive"))
      (node (ref "U2") (pin "23") (pinfunction "IO15_23") (pintype "bidirectional"))
    )
    (net (code "19") (name "MISO") (class "Default")
      (node (ref "D12") (pin "1") (pinfunction "1_1") (pintype "passive"))
      (node (ref "J4") (pin "P7") (pinfunction "DAT0_P7") (pintype "bidirectional"))
      (node (ref "R8") (pin "1") (pinfunction "1_1") (pintype "passive"))
      (node (ref "TP6") (pin "TP") (pinfunction "TP_TP") (pintype "input"))
      (node (ref "U1") (pin "2") (pinfunction "DO(IO1)_2") (pintype "bidirectional"))
      (node (ref "U2") (pin "27") (pinfunction "IO2_27") (pintype "bidirectional"))
    )
    (net (code "20") (name "MOSI") (class "Default")
      (node (ref "D11") (pin "1") (pinfunction "1_1") (pintype "passive"))
      (node (ref "J1") (pin "14") (pinfunction "14_14") (pintype "bidirectional"))
      (node (ref "J4") (pin "P3") (pinfunction "CMD_P3") (pintype "bidirectional"))
      (node (ref "R6") (pin "1") (pinfunction "1_1") (pintype "passive"))
      (node (ref "TP7") (pin "TP") (pinfunction "TP_TP") (pintype "input"))
      (node (ref "U1") (pin "5") (pinfunction "DI(IO0)_5") (pintype "bidirectional"))
      (node (ref "U2") (pin "7") (pinfunction "IO7_7") (pintype "bidirectional"))
    )
    (net (code "21") (name "Net-(CHG_LED-PadC)") (class "Default")
      (node (ref "CHG_LED") (pin "C") (pinfunction "C_C") (pintype "passive"))
      (node (ref "R1_BAT") (pin "2") (pinfunction "2_2") (pintype "passive"))
    )
    (net (code "22") (name "Net-(D2-CATHODE)") (class "Default")
      (node (ref "C1_BAT1") (pin "1") (pinfunction "1_1") (pintype "passive"))
      (node (ref "D2") (pin "1") (pinfunction "CATHODE_1") (pintype "bidirectional"))
      (node (ref "IC4") (pin "1") (pinfunction "VIN_1") (pintype "bidirectional"))
      (node (ref "IC4") (pin "3") (pinfunction "CE_3") (pintype "bidirectional"))
      (node (ref "Q1") (pin "2") (pinfunction "S_2") (pintype "bidirectional"))
    )
    (net (code "23") (name "Net-(D3-K)") (class "Default")
      (node (ref "C4") (pin "1") (pinfunction "1_1") (pintype "passive"))
      (node (ref "D3") (pin "1") (pinfunction "K_1") (pintype "bidirectional"))
      (node (ref "D4") (pin "2") (pinfunction "A_2") (pintype "bidirectional"))
    )
    (net (code "24") (name "Net-(D7-CATHODE)") (class "Default")
      (node (ref "D7") (pin "1") (pinfunction "CATHODE_1") (pintype "bidirectional"))
      (node (ref "R_CAPACITOR") (pin "2") (pinfunction "2_2") (pintype "passive"))
    )
    (net (code "25") (name "Net-(EPD_C1-Pad1)") (class "Default")
      (node (ref "EPD_C1") (pin "1") (pinfunction "1_1") (pintype "passive"))
      (node (ref "J1") (pin "4") (pinfunction "4_4") (pintype "bidirectional"))
    )
    (net (code "26") (name "Net-(EPD_C2-Pad1)") (class "Default")
      (node (ref "EPD_C2") (pin "1") (pinfunction "1_1") (pintype "passive"))
      (node (ref "J1") (pin "5") (pinfunction "5_5") (pintype "bidirectional"))
    )
    (net (code "27") (name "Net-(EPD_C6-Pad1)") (class "Default")
      (node (ref "EPD_C6") (pin "1") (pinfunction "1_1") (pintype "passive"))
      (node (ref "J1") (pin "18") (pinfunction "18_18") (pintype "bidirectional"))
    )
    (net (code "28") (name "Net-(EPD_C7-Pad1)") (class "Default")
      (node (ref "EPD_C7") (pin "1") (pinfunction "1_1") (pintype "passive"))
      (node (ref "J1") (pin "19") (pinfunction "19_19") (pintype "bidirectional"))
    )
    (net (code "29") (name "Net-(EPD_C8-Pad1)") (class "Default")
      (node (ref "EPD_C8") (pin "1") (pinfunction "1_1") (pintype "passive"))
      (node (ref "J1") (pin "20") (pinfunction "20_20") (pintype "bidirectional"))
    )
    (net (code "30") (name "Net-(EPD_C10-Pad1)") (class "Default")
      (node (ref "EPD_C10") (pin "1") (pinfunction "1_1") (pintype "passive"))
      (node (ref "J1") (pin "22") (pinfunction "22_22") (pintype "bidirectional"))
    )
    (net (code "31") (name "Net-(EPD_C12-Pad1)") (class "Default")
      (node (ref "EPD_C12") (pin "1") (pinfunction "1_1") (pintype "passive"))
      (node (ref "J1") (pin "24") (pinfunction "24_24") (pintype "bidirectional"))
    )
    (net (code "32") (name "Net-(IC1-CT)") (class "Default")
      (node (ref "C_DELAY") (pin "1") (pinfunction "1_1") (pintype "passive"))
      (node (ref "IC1") (pin "5") (pinfunction "CT_5") (pintype "bidirectional"))
    )
    (net (code "33") (name "Net-(J2-PadA5)") (class "Default")
      (node (ref "J2") (pin "A5") (pinfunction "A5_A5") (pintype "bidirectional"))
      (node (ref "R2-USB1") (pin "2") (pinfunction "2_2") (pintype "passive"))
    )
    (net (code "34") (name "Net-(J2-PadB5)") (class "Default")
      (node (ref "J2") (pin "B5") (pinfunction "B5_B5") (pintype "bidirectional"))
      (node (ref "R2-USB") (pin "1") (pinfunction "1_1") (pintype "passive"))
    )
    (net (code "35") (name "Net-(MCP73831-PROG)") (class "Default")
      (node (ref "MCP73831") (pin "5") (pinfunction "PROG_5") (pintype "input"))
      (node (ref "R2_BAT") (pin "2") (pinfunction "2_2") (pintype "passive"))
    )
    (net (code "36") (name "Net-(MCP73831-STAT)") (class "Default")
      (node (ref "MCP73831") (pin "1") (pinfunction "STAT_1") (pintype "output"))
      (node (ref "R1_BAT") (pin "1") (pinfunction "1_1") (pintype "passive"))
    )
    (net (code "37") (name "PREVGH") (class "Default")
      (node (ref "D5") (pin "1") (pinfunction "K_1") (pintype "bidirectional"))
      (node (ref "EPD_C9") (pin "1") (pinfunction "1_1") (pintype "passive"))
      (node (ref "J1") (pin "21") (pinfunction "21_21") (pintype "bidirectional"))
    )
    (net (code "38") (name "PREVGL") (class "Default")
      (node (ref "D3") (pin "2") (pinfunction "A_2") (pintype "bidirectional"))
      (node (ref "EPD_C11") (pin "1") (pinfunction "1_1") (pintype "passive"))
      (node (ref "J1") (pin "23") (pinfunction "23_23") (pintype "bidirectional"))
    )
    (net (code "39") (name "RESE") (class "Default")
      (node (ref "J1") (pin "3") (pinfunction "3_3") (pintype "bidirectional"))
      (node (ref "Q3") (pin "2") (pinfunction "S_2") (pintype "bidirectional"))
      (node (ref "R3") (pin "1") (pinfunction "1_1") (pintype "passive"))
    )
    (net (code "40") (name "RESE'") (class "Default")
      (node (ref "R2") (pin "2") (pinfunction "2_2") (pintype "passive"))
      (node (ref "R3") (pin "2") (pinfunction "2_2") (pintype "passive"))
      (node (ref "SJ1") (pin "2") (pinfunction "2_2") (pintype "passive"))
    )
    (net (code "41") (name "RESET") (class "Default")
      (node (ref "C5") (pin "1") (pinfunction "1_1") (pintype "passive"))
      (node (ref "IC1") (pin "1") (pinfunction "VOUT_1") (pintype "bidirectional"))
      (node (ref "RESET_BUTTON") (pin "4") (pinfunction "4_4") (pintype "passive"))
      (node (ref "R_RESET") (pin "2") (pinfunction "2_2") (pintype "passive"))
      (node (ref "U2") (pin "3") (pinfunction "EN_3") (pintype "input"))
    )
    (net (code "42") (name "RTC_RST") (class "Default")
      (node (ref "U2") (pin "16") (pinfunction "IO18_16") (pintype "bidirectional"))
      (node (ref "U3") (pin "4") (pinfunction "~{RST}_4") (pintype "input"))
    )
    (net (code "43") (name "RX") (class "Default")
      (node (ref "TP2") (pin "TP") (pinfunction "TP_TP") (pintype "input"))
      (node (ref "U2") (pin "24") (pinfunction "RXD0/GPIO17_24") (pintype "bidirectional"))
    )
    (net (code "44") (name "SCK") (class "Default")
      (node (ref "D10") (pin "1") (pinfunction "1_1") (pintype "passive"))
      (node (ref "J1") (pin "13") (pinfunction "13_13") (pintype "bidirectional"))
      (node (ref "J4") (pin "P5") (pinfunction "CLK_P5") (pintype "bidirectional"))
      (node (ref "R7") (pin "1") (pinfunction "1_1") (pintype "passive"))
      (node (ref "TP8") (pin "TP") (pinfunction "TP_TP") (pintype "input"))
      (node (ref "U1") (pin "6") (pinfunction "CLK_6") (pintype "input"))
      (node (ref "U2") (pin "6") (pinfunction "IO6_6") (pintype "bidirectional"))
    )
    (net (code "45") (name "SCL") (class "Default")
      (node (ref "J3") (pin "4") (pinfunction "4_4") (pintype "passive"))
      (node (ref "R2_PINH") (pin "1") (pinfunction "1_1") (pintype "passive"))
      (node (ref "SENSOR2") (pin "4") (pinfunction "SCK_4") (pintype "input"))
      (node (ref "U2") (pin "20") (pinfunction "IO22_20") (pintype "bidirectional"))
      (node (ref "U3") (pin "16") (pinfunction "SCL_16") (pintype "input"))
      (node (ref "U4") (pin "7") (pinfunction "SCL_7") (pintype "input"))
    )
    (net (code "46") (name "SDA") (class "Default")
      (node (ref "J3") (pin "3") (pinfunction "3_3") (pintype "passive"))
      (node (ref "R1_PINH") (pin "1") (pinfunction "1_1") (pintype "passive"))
      (node (ref "SENSOR2") (pin "3") (pinfunction "SDI_3") (pintype "bidirectional"))
      (node (ref "U2") (pin "19") (pinfunction "IO21_19") (pintype "bidirectional"))
      (node (ref "U3") (pin "15") (pinfunction "SDA_15") (pintype "bidirectional"))
      (node (ref "U4") (pin "8") (pinfunction "SDA_8") (pintype "bidirectional"))
    )
    (net (code "47") (name "SRC") (class "Default")
      (node (ref "C4") (pin "2") (pinfunction "2_2") (pintype "passive"))
      (node (ref "D5") (pin "2") (pinfunction "A_2") (pintype "bidirectional"))
      (node (ref "L1") (pin "1") (pinfunction "1_1") (pintype "passive"))
      (node (ref "Q3") (pin "3") (pinfunction "D_3") (pintype "bidirectional"))
    )
    (net (code "48") (name "SS_SD") (class "Default")
      (node (ref "D6") (pin "1") (pinfunction "1_1") (pintype "passive"))
      (node (ref "J4") (pin "P2") (pinfunction "CD/DAT3_P2") (pintype "bidirectional"))
      (node (ref "R10") (pin "1") (pinfunction "1_1") (pintype "passive"))
      (node (ref "U2") (pin "4") (pinfunction "IO4_4") (pintype "bidirectional"))
    )
    (net (code "49") (name "TX") (class "Default")
      (node (ref "TP1") (pin "TP") (pinfunction "TP_TP") (pintype "input"))
      (node (ref "U2") (pin "25") (pinfunction "TXD0/GPIO16_25") (pintype "bidirectional"))
    )
    (net (code "50") (name "USB_D+") (class "Default")
      (node (ref "D1") (pin "1") (pinfunction "I/O1_1_1") (pintype "bidirectional"))
      (node (ref "U2") (pin "14") (pinfunction "IO13_14") (pintype "bidirectional"))
    )
    (net (code "51") (name "USB_D-") (class "Default")
      (node (ref "D1") (pin "3") (pinfunction "I/O2_1_3") (pintype "bidirectional"))
      (node (ref "U2") (pin "13") (pinfunction "IO12_13") (pintype "bidirectional"))
    )
    (net (code "52") (name "VBAT") (class "Default")
      (node (ref "C2_BAT") (pin "1") (pinfunction "1_1") (pintype "passive"))
      (node (ref "MCP73831") (pin "3") (pinfunction "VBAT_3") (pintype "power_in"))
      (node (ref "Q1") (pin "3") (pinfunction "D_3") (pintype "bidirectional"))
      (node (ref "TP3") (pin "TP") (pinfunction "TP_TP") (pintype "input"))
      (node (ref "U4") (pin "2") (pinfunction "CELL_2") (pintype "power_in"))
      (node (ref "U4") (pin "3") (pinfunction "VDD_3") (pintype "power_in"))
    )
    (net (code "53") (name "VBUS") (class "Default")
      (node (ref "C1_BAT") (pin "1") (pinfunction "1_1") (pintype "passive"))
      (node (ref "C4_USB") (pin "1") (pinfunction "1_1") (pintype "passive"))
      (node (ref "C5_USB") (pin "1") (pinfunction "1_1") (pintype "passive"))
      (node (ref "CHG_LED") (pin "A") (pinfunction "A_A") (pintype "passive"))
      (node (ref "D1") (pin "5") (pinfunction "VBUS_5") (pintype "bidirectional"))
      (node (ref "D2") (pin "2") (pinfunction "ANODE_2") (pintype "bidirectional"))
      (node (ref "MCP73831") (pin "4") (pinfunction "VIN_4") (pintype "power_in"))
      (node (ref "PFMF.050.1") (pin "2") (pinfunction "2_2") (pintype "passive"))
      (node (ref "Q1") (pin "1") (pinfunction "G_1") (pintype "bidirectional"))
      (node (ref "R1_PWRUSB") (pin "1") (pinfunction "1_1") (pintype "passive"))
      (node (ref "TP14") (pin "TP") (pinfunction "TP_TP") (pintype "input"))
    )
    (net (code "54") (name "VRTC") (class "Default")
      (node (ref "C10_SUPERCAP") (pin "2") (pinfunction "2_2") (pintype "passive"))
      (node (ref "C8") (pin "1") (pinfunction "1_1") (pintype "passive"))
      (node (ref "R_CAPACITOR") (pin "1") (pinfunction "1_1") (pintype "passive"))
      (node (ref "U3") (pin "14") (pinfunction "VBAT_14") (pintype "power_in"))
    )
    (net (code "55") (name "VUSB") (class "Default")
      (node (ref "J2") (pin "A4") (pinfunction "A4_A4") (pintype "bidirectional"))
      (node (ref "J2") (pin "A9") (pinfunction "A9_A9") (pintype "bidirectional"))
      (node (ref "J2") (pin "B4") (pinfunction "B4_B4") (pintype "bidirectional"))
      (node (ref "J2") (pin "B9") (pinfunction "B9_B9") (pintype "bidirectional"))
      (node (ref "PFMF.050.1") (pin "1") (pinfunction "1_1") (pintype "passive"))
    )
    (net (code "56") (name "unconnected-(IC1-NC-Pad4)") (class "Default")
      (node (ref "IC1") (pin "4") (pinfunction "NC_4") (pintype "no_connect"))
    )
    (net (code "57") (name "unconnected-(IC4-NC-Pad4)") (class "Default")
      (node (ref "IC4") (pin "4") (pinfunction "NC_4") (pintype "no_connect"))
    )
    (net (code "58") (name "unconnected-(J1-Pad1)") (class "Default")
      (node (ref "J1") (pin "1") (pinfunction "1_1") (pintype "bidirectional"))
    )
    (net (code "59") (name "unconnected-(J1-Pad6)") (class "Default")
      (node (ref "J1") (pin "6") (pinfunction "6_6") (pintype "bidirectional"))
    )
    (net (code "60") (name "unconnected-(J1-Pad7)") (class "Default")
      (node (ref "J1") (pin "7") (pinfunction "7_7") (pintype "bidirectional"))
    )
    (net (code "61") (name "unconnected-(J2-PadA8)") (class "Default")
      (node (ref "J2") (pin "A8") (pinfunction "A8_A8") (pintype "bidirectional"))
    )
    (net (code "62") (name "unconnected-(J2-PadB8)") (class "Default")
      (node (ref "J2") (pin "B8") (pinfunction "B8_B8") (pintype "bidirectional"))
    )
    (net (code "63") (name "unconnected-(J4-DAT1-PadP8)") (class "Default")
      (node (ref "J4") (pin "P8") (pinfunction "DAT1_P8") (pintype "bidirectional"))
    )
    (net (code "64") (name "unconnected-(J4-DAT2-PadP1)") (class "Default")
      (node (ref "J4") (pin "P1") (pinfunction "DAT2_P1") (pintype "bidirectional"))
    )
    (net (code "65") (name "unconnected-(J4-DETECTION_1-PadS1)") (class "Default")
      (node (ref "J4") (pin "S1") (pinfunction "DETECTION_1_S1") (pintype "bidirectional"))
    )
    (net (code "66") (name "unconnected-(J4-DETECTION_2-PadS2)") (class "Default")
      (node (ref "J4") (pin "S2") (pinfunction "DETECTION_2_S2") (pintype "bidirectional"))
    )
    (net (code "67") (name "unconnected-(RESET_BUTTON-Pad3)") (class "Default")
      (node (ref "RESET_BUTTON") (pin "3") (pinfunction "3_3") (pintype "passive"))
    )
    (net (code "68") (name "unconnected-(U2-NC-Pad22)") (class "Default")
      (node (ref "U2") (pin "22") (pinfunction "NC_22") (pintype "no_connect"))
    )
    (net (code "69") (name "unconnected-(U4-~{ALERT}-Pad5)") (class "Default")
      (node (ref "U4") (pin "5") (pinfunction "~{ALERT}_5") (pintype "output"))
    )
  )
)
